# Temperatura_y_humedad.net
KiCad netlist of a schematic drawn in EAGLE
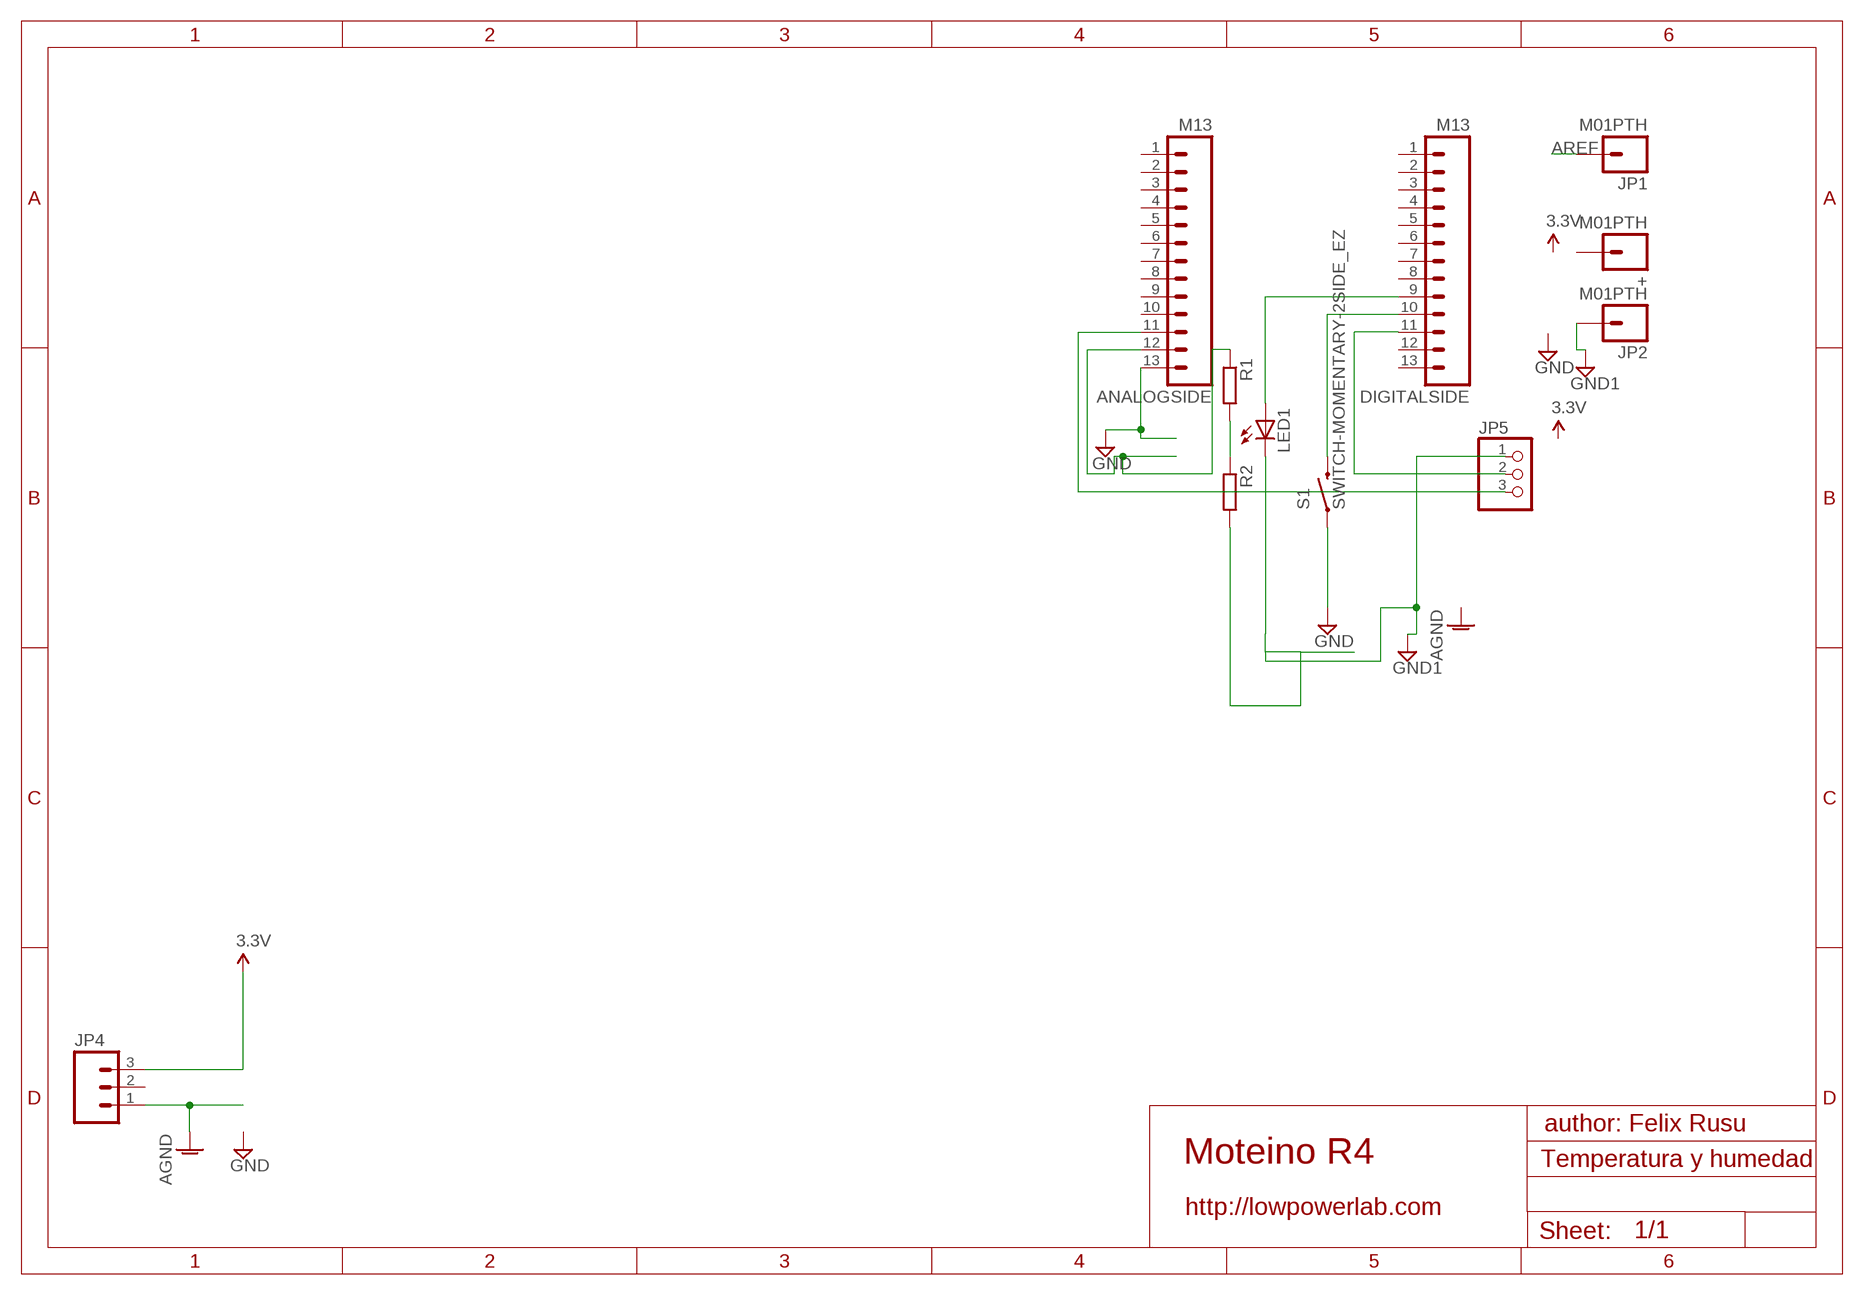
[diagram p0: schematic, sheet 1]

(export (version "E")
  (design (tool "Eeschema 10.0.6"))
  (components
    (comp (ref "+")
      (value "M01PTH")
      (footprint "eagle-import:1X01")
      (libsource (lib "eagle-import") (part "M01PTH"))
    )
    (comp (ref "ANALOGSIDE")
      (value "M13")
      (footprint "eagle-import:1X13")
      (libsource (lib "eagle-import") (part "M13"))
    )
    (comp (ref "DIGITALSIDE")
      (value "M13")
      (footprint "eagle-import:1X13")
      (libsource (lib "eagle-import") (part "M13"))
    )
    (comp (ref "JP1")
      (value "M01PTH")
      (footprint "eagle-import:1X01")
      (libsource (lib "eagle-import") (part "M01PTH"))
    )
    (comp (ref "JP2")
      (value "M01PTH")
      (footprint "eagle-import:1X01")
      (libsource (lib "eagle-import") (part "M01PTH"))
    )
    (comp (ref "JP4")
      (value "M03PTH")
      (footprint "eagle-import:1X03")
      (libsource (lib "eagle-import") (part "M03PTH"))
    )
    (comp (ref "JP5")
      (value "PINHD-1X3")
      (footprint "eagle-import:1X03")
      (libsource (lib "eagle-import") (part "PINHD-1X3"))
    )
    (comp (ref "LED1")
      (value "LED3MM")
      (footprint "eagle-import:LED3MM")
      (libsource (lib "eagle-import") (part "LED3MM"))
    )
    (comp (ref "R1")
      (value "R-EU_0204/7")
      (footprint "eagle-import:0204_7")
      (libsource (lib "eagle-import") (part "R-EU_0204/7"))
    )
    (comp (ref "R2")
      (value "R-EU_0204/7")
      (footprint "eagle-import:0204_7")
      (libsource (lib "eagle-import") (part "R-EU_0204/7"))
    )
    (comp (ref "S1")
      (value "SWITCH-MOMENTARY-2SIDE_EZ")
      (footprint "eagle-import:TACTILE-PTH-SIDEEZ")
      (libsource (lib "eagle-import") (part "SWITCH-MOMENTARY-2SIDE_EZ"))
    )
  )
  (nets
    (net (code "1") (name "/AREF") (class "Default")
      (node (ref "JP1") (pin "1") (pinfunction "1_1") (pintype "passive"))
    )
    (net (code "2") (name "3.3V") (class "Default")
      (node (ref "JP4") (pin "3") (pinfunction "3_3") (pintype "passive"))
    )
    (net (code "3") (name "AGND") (class "Default")
      (node (ref "JP4") (pin "1") (pinfunction "1_1") (pintype "passive"))
    )
    (net (code "4") (name "GND") (class "Default")
      (node (ref "ANALOGSIDE") (pin "13") (pinfunction "13_13") (pintype "passive"))
      (node (ref "S1") (pin "1") (pinfunction "1_1") (pintype "passive"))
    )
    (net (code "5") (name "GND1") (class "Default")
      (node (ref "JP2") (pin "1") (pinfunction "1_1") (pintype "passive"))
      (node (ref "JP5") (pin "1") (pinfunction "1_1") (pintype "passive"))
      (node (ref "LED1") (pin "K") (pinfunction "C_K") (pintype "passive"))
      (node (ref "R2") (pin "2") (pinfunction "2_2") (pintype "passive"))
    )
    (net (code "6") (name "Net-(ANALOGSIDE-Pad11)") (class "Default")
      (node (ref "ANALOGSIDE") (pin "11") (pinfunction "11_11") (pintype "passive"))
      (node (ref "JP5") (pin "3") (pinfunction "3_3") (pintype "passive"))
    )
    (net (code "7") (name "Net-(ANALOGSIDE-Pad12)") (class "Default")
      (node (ref "ANALOGSIDE") (pin "12") (pinfunction "12_12") (pintype "passive"))
      (node (ref "R1") (pin "1") (pinfunction "1_1") (pintype "passive"))
    )
    (net (code "8") (name "Net-(DIGITALSIDE-Pad9)") (class "Default")
      (node (ref "DIGITALSIDE") (pin "9") (pinfunction "9_9") (pintype "passive"))
      (node (ref "LED1") (pin "A") (pinfunction "A_A") (pintype "passive"))
    )
    (net (code "9") (name "Net-(DIGITALSIDE-Pad10)") (class "Default")
      (node (ref "DIGITALSIDE") (pin "10") (pinfunction "10_10") (pintype "passive"))
      (node (ref "S1") (pin "2") (pinfunction "2_2") (pintype "passive"))
    )
    (net (code "10") (name "Net-(DIGITALSIDE-Pad11)") (class "Default")
      (node (ref "DIGITALSIDE") (pin "11") (pinfunction "11_11") (pintype "passive"))
      (node (ref "JP5") (pin "2") (pinfunction "2_2") (pintype "passive"))
    )
    (net (code "11") (name "Net-(R1-Pad2)") (class "Default")
      (node (ref "R1") (pin "2") (pinfunction "2_2") (pintype "passive"))
      (node (ref "R2") (pin "1") (pinfunction "1_1") (pintype "passive"))
    )
    (net (code "12") (name "unconnected-(+-Pad1)") (class "Default")
      (node (ref "+") (pin "1") (pinfunction "1_1") (pintype "passive"))
    )
    (net (code "13") (name "unconnected-(ANALOGSIDE-Pad1)") (class "Default")
      (node (ref "ANALOGSIDE") (pin "1") (pinfunction "1_1") (pintype "passive"))
    )
    (net (code "14") (name "unconnected-(ANALOGSIDE-Pad2)") (class "Default")
      (node (ref "ANALOGSIDE") (pin "2") (pinfunction "2_2") (pintype "passive"))
    )
    (net (code "15") (name "unconnected-(ANALOGSIDE-Pad3)") (class "Default")
      (node (ref "ANALOGSIDE") (pin "3") (pinfunction "3_3") (pintype "passive"))
    )
    (net (code "16") (name "unconnected-(ANALOGSIDE-Pad4)") (class "Default")
      (node (ref "ANALOGSIDE") (pin "4") (pinfunction "4_4") (pintype "passive"))
    )
    (net (code "17") (name "unconnected-(ANALOGSIDE-Pad5)") (class "Default")
      (node (ref "ANALOGSIDE") (pin "5") (pinfunction "5_5") (pintype "passive"))
    )
    (net (code "18") (name "unconnected-(ANALOGSIDE-Pad6)") (class "Default")
      (node (ref "ANALOGSIDE") (pin "6") (pinfunction "6_6") (pintype "passive"))
    )
    (net (code "19") (name "unconnected-(ANALOGSIDE-Pad7)") (class "Default")
      (node (ref "ANALOGSIDE") (pin "7") (pinfunction "7_7") (pintype "passive"))
    )
    (net (code "20") (name "unconnected-(ANALOGSIDE-Pad8)") (class "Default")
      (node (ref "ANALOGSIDE") (pin "8") (pinfunction "8_8") (pintype "passive"))
    )
    (net (code "21") (name "unconnected-(ANALOGSIDE-Pad9)") (class "Default")
      (node (ref "ANALOGSIDE") (pin "9") (pinfunction "9_9") (pintype "passive"))
    )
    (net (code "22") (name "unconnected-(ANALOGSIDE-Pad10)") (class "Default")
      (node (ref "ANALOGSIDE") (pin "10") (pinfunction "10_10") (pintype "passive"))
    )
    (net (code "23") (name "unconnected-(DIGITALSIDE-Pad1)") (class "Default")
      (node (ref "DIGITALSIDE") (pin "1") (pinfunction "1_1") (pintype "passive"))
    )
    (net (code "24") (name "unconnected-(DIGITALSIDE-Pad2)") (class "Default")
      (node (ref "DIGITALSIDE") (pin "2") (pinfunction "2_2") (pintype "passive"))
    )
    (net (code "25") (name "unconnected-(DIGITALSIDE-Pad3)") (class "Default")
      (node (ref "DIGITALSIDE") (pin "3") (pinfunction "3_3") (pintype "passive"))
    )
    (net (code "26") (name "unconnected-(DIGITALSIDE-Pad4)") (class "Default")
      (node (ref "DIGITALSIDE") (pin "4") (pinfunction "4_4") (pintype "passive"))
    )
    (net (code "27") (name "unconnected-(DIGITALSIDE-Pad5)") (class "Default")
      (node (ref "DIGITALSIDE") (pin "5") (pinfunction "5_5") (pintype "passive"))
    )
    (net (code "28") (name "unconnected-(DIGITALSIDE-Pad6)") (class "Default")
      (node (ref "DIGITALSIDE") (pin "6") (pinfunction "6_6") (pintype "passive"))
    )
    (net (code "29") (name "unconnected-(DIGITALSIDE-Pad7)") (class "Default")
      (node (ref "DIGITALSIDE") (pin "7") (pinfunction "7_7") (pintype "passive"))
    )
    (net (code "30") (name "unconnected-(DIGITALSIDE-Pad8)") (class "Default")
      (node (ref "DIGITALSIDE") (pin "8") (pinfunction "8_8") (pintype "passive"))
    )
    (net (code "31") (name "unconnected-(DIGITALSIDE-Pad12)") (class "Default")
      (node (ref "DIGITALSIDE") (pin "12") (pinfunction "12_12") (pintype "passive"))
    )
    (net (code "32") (name "unconnected-(DIGITALSIDE-Pad13)") (class "Default")
      (node (ref "DIGITALSIDE") (pin "13") (pinfunction "13_13") (pintype "passive"))
    )
    (net (code "33") (name "unconnected-(JP4-Pad2)") (class "Default")
      (node (ref "JP4") (pin "2") (pinfunction "2_2") (pintype "passive"))
    )
  )
)
